# 20251027-temp_board.net
KiCad netlist of a schematic drawn in EAGLE
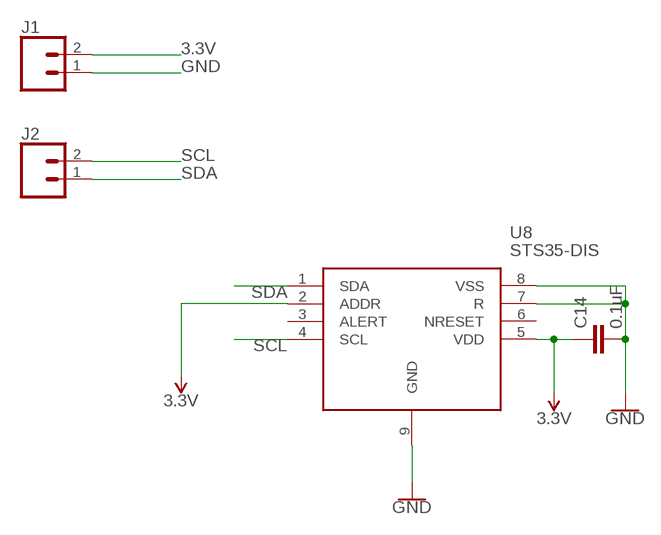
[diagram p0: schematic, sheet 1]

(export (version "E")
  (design (tool "Eeschema 10.0.6"))
  (components
    (comp (ref "C14")
      (value "0.1uF")
      (footprint "eagle-import:0603")
      (libsource (lib "eagle-import") (part "0.1UF-0603-25V-5%"))
    )
    (comp (ref "J1")
      (value "CONN_02_1.5MM")
      (footprint "eagle-import:1X02_1.5MM_NO_SILK")
      (libsource (lib "eagle-import") (part "CONN_02_1.5MM"))
    )
    (comp (ref "J2")
      (value "CONN_02_1.5MM")
      (footprint "eagle-import:1X02_1.5MM_NO_SILK")
      (libsource (lib "eagle-import") (part "CONN_02_1.5MM"))
    )
    (comp (ref "U8")
      (value "STS35-DIS")
      (footprint "eagle-import:SON50P250X250X100-9N")
      (fields (field (name "MOUSER_PART_NUMBER") "403-STS35-DIS"))
      (libsource (lib "eagle-import") (part "STS35-DIS"))
    )
  )
  (nets
    (net (code "1") (name "/SCL") (class "Default")
      (node (ref "J2") (pin "2") (pinfunction "2_2") (pintype "passive"))
      (node (ref "U8") (pin "4") (pinfunction "SCL_4") (pintype "bidirectional"))
    )
    (net (code "2") (name "/SDA") (class "Default")
      (node (ref "J2") (pin "1") (pinfunction "1_1") (pintype "passive"))
      (node (ref "U8") (pin "1") (pinfunction "SDA_1") (pintype "bidirectional"))
    )
    (net (code "3") (name "3.3V") (class "Default")
      (node (ref "C14") (pin "1") (pinfunction "1_1") (pintype "passive"))
      (node (ref "J1") (pin "2") (pinfunction "2_2") (pintype "passive"))
      (node (ref "U8") (pin "2") (pinfunction "ADDR_2") (pintype "bidirectional"))
      (node (ref "U8") (pin "5") (pinfunction "VDD_5") (pintype "bidirectional"))
    )
    (net (code "4") (name "GND") (class "Default")
      (node (ref "C14") (pin "2") (pinfunction "2_2") (pintype "passive"))
      (node (ref "J1") (pin "1") (pinfunction "1_1") (pintype "passive"))
      (node (ref "U8") (pin "7") (pinfunction "R_7") (pintype "bidirectional"))
      (node (ref "U8") (pin "8") (pinfunction "VSS_8") (pintype "bidirectional"))
      (node (ref "U8") (pin "9") (pinfunction "GND_9") (pintype "bidirectional"))
    )
    (net (code "5") (name "unconnected-(U8-ALERT-Pad3)") (class "Default")
      (node (ref "U8") (pin "3") (pinfunction "ALERT_3") (pintype "bidirectional"))
    )
    (net (code "6") (name "unconnected-(U8-NRESET-Pad6)") (class "Default")
      (node (ref "U8") (pin "6") (pinfunction "NRESET_6") (pintype "bidirectional"))
    )
  )
)
